# PIN.net
KiCad netlist of a schematic drawn in Altium Designer
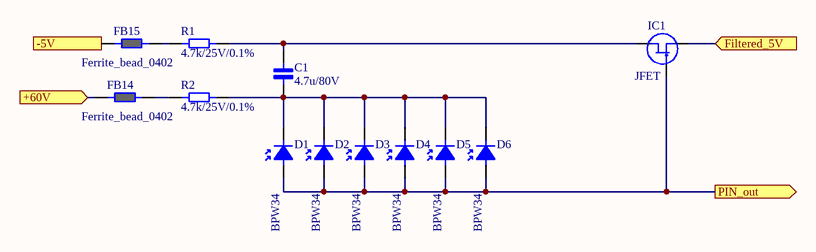
[diagram p0: PIN.SchDoc]

(export (version "E")
  (design (tool "Eeschema 10.0.6"))
  (components
    (comp (ref "C1")
      (value "4.7u/80V")
      (footprint "CAP_1210")
      (description "Multilayer Ceramic Capacitors MLCC - SMD/SMT 1210 4.7uF 80volts *Derate Voltage/Temp")
      (fields
        (field (name "MANUFACTURER") "Murata")
        (field (name "MANUFACTURER PART NUMBER") "GRM32ER71K475KE14L")
      )
      (libsource (lib "Cubesat_lib") (part "Cap_1210_4.7u"))
    )
    (comp (ref "D1")
      (value "BPW34")
      (footprint "BPW34")
      (description "VBPW34S, Pin photodiode, 60V reverse bias max")
      (libsource (lib "Cubesat_lib") (part "BPW34 PIN Photodiode"))
    )
    (comp (ref "D2")
      (value "BPW34")
      (footprint "BPW34")
      (description "VBPW34S, Pin photodiode, 60V reverse bias max")
      (libsource (lib "Cubesat_lib") (part "BPW34 PIN Photodiode"))
    )
    (comp (ref "D3")
      (value "BPW34")
      (footprint "BPW34")
      (description "VBPW34S, Pin photodiode, 60V reverse bias max")
      (libsource (lib "Cubesat_lib") (part "BPW34 PIN Photodiode"))
    )
    (comp (ref "D4")
      (value "BPW34")
      (footprint "BPW34")
      (description "VBPW34S, Pin photodiode, 60V reverse bias max")
      (libsource (lib "Cubesat_lib") (part "BPW34 PIN Photodiode"))
    )
    (comp (ref "D5")
      (value "BPW34")
      (footprint "BPW34")
      (description "VBPW34S, Pin photodiode, 60V reverse bias max")
      (libsource (lib "Cubesat_lib") (part "BPW34 PIN Photodiode"))
    )
    (comp (ref "D6")
      (value "BPW34")
      (footprint "BPW34")
      (description "VBPW34S, Pin photodiode, 60V reverse bias max")
      (libsource (lib "Cubesat_lib") (part "BPW34 PIN Photodiode"))
    )
    (comp (ref "FB14")
      (value "Ferrite_bead_0402")
      (footprint "FERRITE_0402")
      (description "Ferrite bead, wurth 74269241102")
      (libsource (lib "Cubesat_lib") (part "Ferrite_bead_0402"))
    )
    (comp (ref "FB15")
      (value "Ferrite_bead_0402")
      (footprint "FERRITE_0402")
      (description "Ferrite bead, wurth 74269241102")
      (libsource (lib "Cubesat_lib") (part "Ferrite_bead_0402"))
    )
    (comp (ref "IC1")
      (value "JFET")
      (footprint "SOT23-3")
      (description "Trans JFET N-CH 25V 3-Pin TO-236AB")
      (fields
        (field (name "MANUFACTURER") "NXP Semiconductors")
        (field (name "MANUFACTURER PART NUMBER") "BF861C")
      )
      (libsource (lib "Cubesat_lib") (part "BF861C"))
    )
    (comp (ref "R1")
      (value "4.7k/25V/0.1%")
      (footprint "RES_0603")
      (description "Vishay, thin film resistor 4.7k/25V/0.1%")
      (libsource (lib "Cubesat_lib") (part "Res_0603_4.7k"))
    )
    (comp (ref "R2")
      (value "4.7k/25V/0.1%")
      (footprint "RES_0603")
      (description "Vishay, thin film resistor 4.7k/25V/0.1%")
      (libsource (lib "Cubesat_lib") (part "Res_0603_4.7k"))
    )
  )
  (nets
    (net (code "1") (name "/+60V") (class "Default")
      (node (ref "FB14") (pin "1") (pinfunction "1_1") (pintype "passive"))
    )
    (net (code "2") (name "/-5V") (class "Default")
      (node (ref "FB15") (pin "1") (pinfunction "1_1") (pintype "passive"))
    )
    (net (code "3") (name "/Filtered_5V") (class "Default")
      (node (ref "IC1") (pin "2") (pinfunction "D_2") (pintype "passive"))
    )
    (net (code "4") (name "/PIN_out") (class "Default")
      (node (ref "D1") (pin "1") (pinfunction "1_1") (pintype "passive"))
      (node (ref "D2") (pin "1") (pinfunction "1_1") (pintype "passive"))
      (node (ref "D3") (pin "1") (pinfunction "1_1") (pintype "passive"))
      (node (ref "D4") (pin "1") (pinfunction "1_1") (pintype "passive"))
      (node (ref "D5") (pin "1") (pinfunction "1_1") (pintype "passive"))
      (node (ref "D6") (pin "1") (pinfunction "1_1") (pintype "passive"))
      (node (ref "IC1") (pin "3") (pinfunction "G_3") (pintype "passive"))
    )
    (net (code "5") (name "Net-(C1-Pad1)") (class "Default")
      (node (ref "C1") (pin "1") (pinfunction "1_1") (pintype "passive"))
      (node (ref "D1") (pin "2") (pinfunction "2_2") (pintype "passive"))
      (node (ref "D2") (pin "2") (pinfunction "2_2") (pintype "passive"))
      (node (ref "D3") (pin "2") (pinfunction "2_2") (pintype "passive"))
      (node (ref "D4") (pin "2") (pinfunction "2_2") (pintype "passive"))
      (node (ref "D5") (pin "2") (pinfunction "2_2") (pintype "passive"))
      (node (ref "D6") (pin "2") (pinfunction "2_2") (pintype "passive"))
      (node (ref "R2") (pin "2") (pinfunction "2_2") (pintype "passive"))
    )
    (net (code "6") (name "Net-(FB14-Pad2)") (class "Default")
      (node (ref "FB14") (pin "2") (pinfunction "2_2") (pintype "passive"))
      (node (ref "R2") (pin "1") (pinfunction "1_1") (pintype "passive"))
    )
    (net (code "7") (name "Net-(FB15-Pad2)") (class "Default")
      (node (ref "FB15") (pin "2") (pinfunction "2_2") (pintype "passive"))
      (node (ref "R1") (pin "1") (pinfunction "1_1") (pintype "passive"))
    )
    (net (code "8") (name "Net-(IC1-S)") (class "Default")
      (node (ref "C1") (pin "2") (pinfunction "2_2") (pintype "passive"))
      (node (ref "IC1") (pin "1") (pinfunction "S_1") (pintype "passive"))
      (node (ref "R1") (pin "2") (pinfunction "2_2") (pintype "passive"))
    )
  )
)
